# Power_board.net
KiCad netlist of a schematic drawn in EAGLE
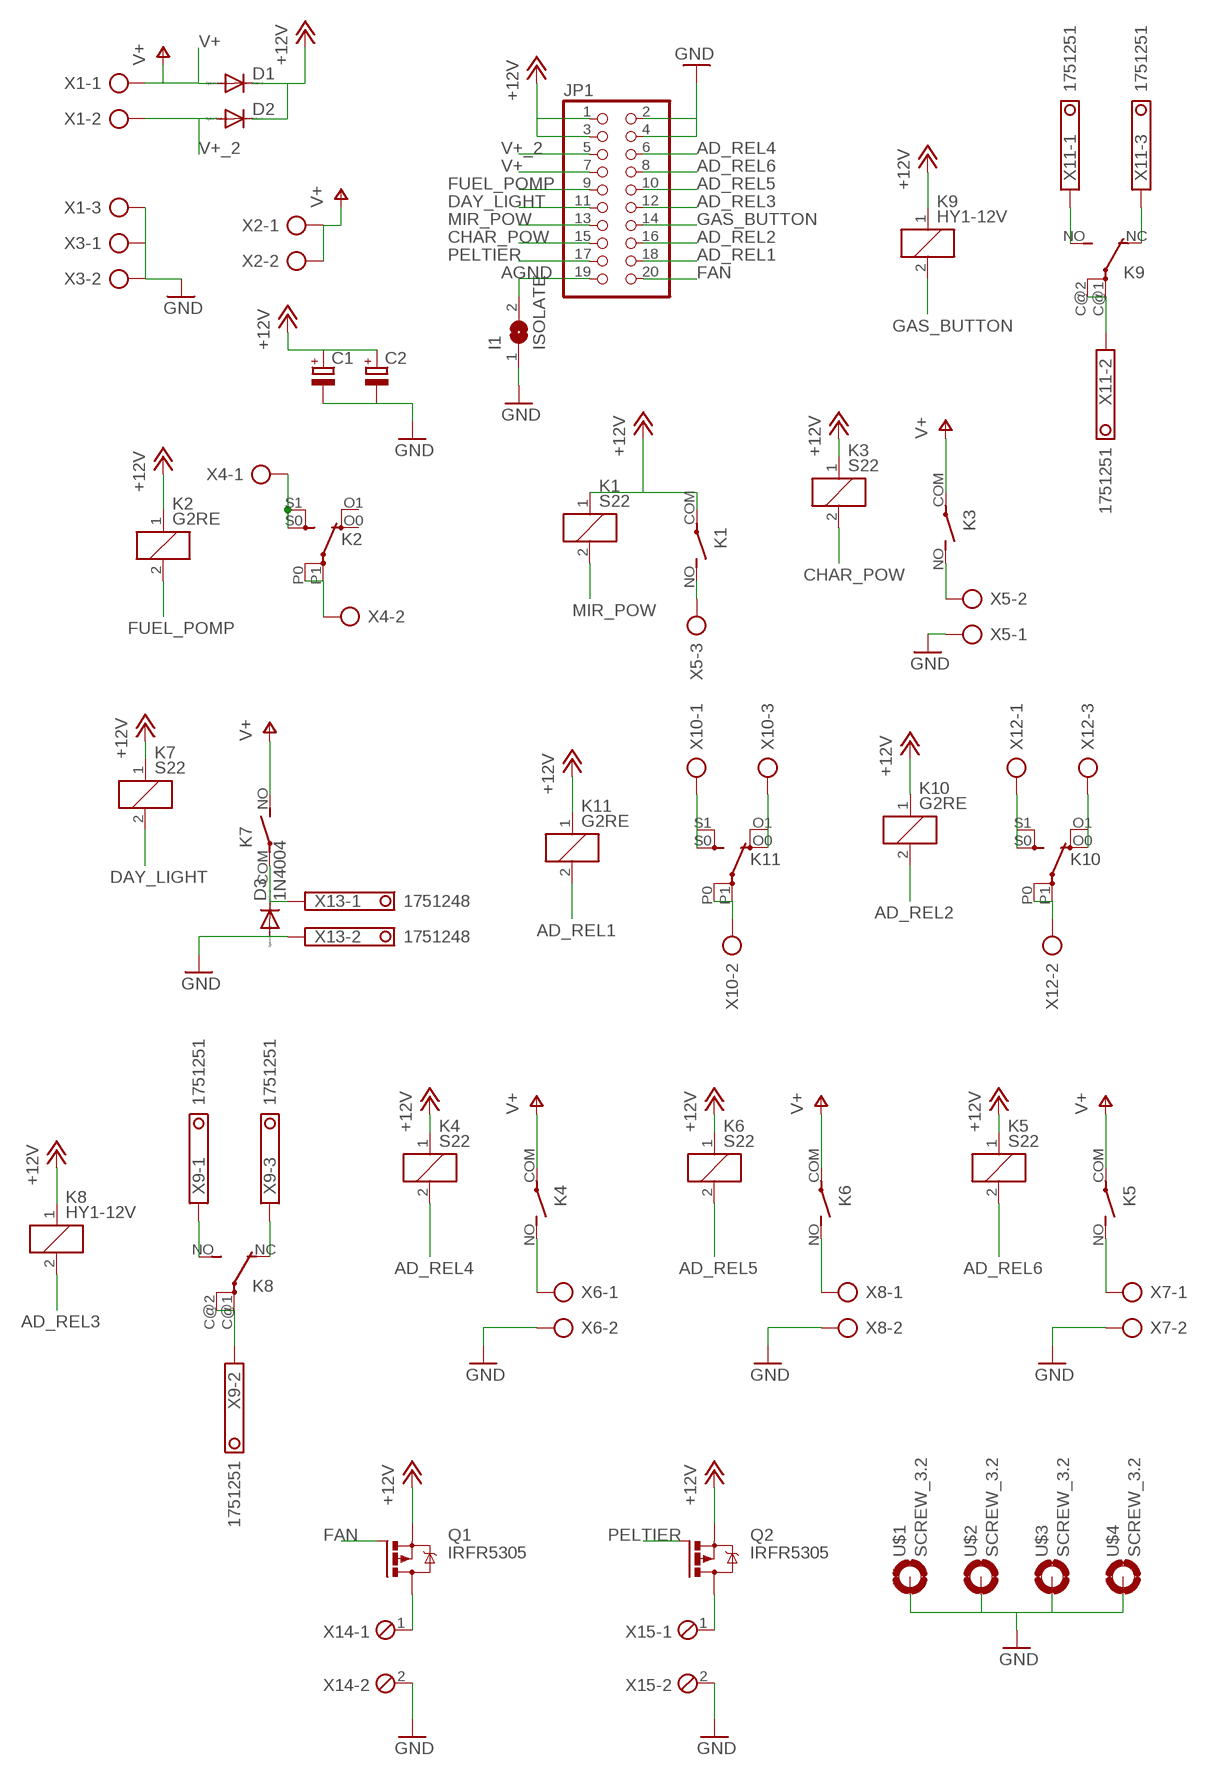
[diagram p0: schematic, sheet 1]

(export (version "E")
  (design (tool "Eeschema 10.0.6"))
  (components
    (comp (ref "C1")
      (value "CAP_HORIZ")
      (footprint "eagle-import:C075-032X103")
      (libsource (lib "eagle-import") (part "CAP_HORIZ"))
    )
    (comp (ref "C2")
      (value "CAP_HORIZ")
      (footprint "eagle-import:C075-032X103")
      (libsource (lib "eagle-import") (part "CAP_HORIZ"))
    )
    (comp (ref "D1")
      (value "DIODE-P6-15")
      (footprint "eagle-import:P6-15")
      (libsource (lib "eagle-import") (part "DIODE-P6-15"))
    )
    (comp (ref "D2")
      (value "DIODE-P6-15")
      (footprint "eagle-import:P6-15")
      (libsource (lib "eagle-import") (part "DIODE-P6-15"))
    )
    (comp (ref "D3")
      (value "1N4004")
      (footprint "eagle-import:DO41-10")
      (libsource (lib "eagle-import") (part "1N4004"))
    )
    (comp (ref "I1")
      (value "ISOLATE")
      (footprint "eagle-import:SJ")
      (libsource (lib "eagle-import") (part "ISOLATE"))
    )
    (comp (ref "JP1")
      (value "PINHD-2X10")
      (footprint "eagle-import:2X10")
      (libsource (lib "eagle-import") (part "PINHD-2X10"))
    )
    (comp (ref "K1")
      (value "S22")
      (footprint "eagle-import:LD")
      (libsource (lib "eagle-import") (part "S22"))
    )
    (comp (ref "K2")
      (value "G2RE")
      (footprint "eagle-import:G2RE")
      (libsource (lib "eagle-import") (part "G2RE"))
    )
    (comp (ref "K3")
      (value "S22")
      (footprint "eagle-import:LD")
      (libsource (lib "eagle-import") (part "S22"))
    )
    (comp (ref "K4")
      (value "S22")
      (footprint "eagle-import:LD")
      (libsource (lib "eagle-import") (part "S22"))
    )
    (comp (ref "K5")
      (value "S22")
      (footprint "eagle-import:LD")
      (libsource (lib "eagle-import") (part "S22"))
    )
    (comp (ref "K6")
      (value "S22")
      (footprint "eagle-import:LD")
      (libsource (lib "eagle-import") (part "S22"))
    )
    (comp (ref "K7")
      (value "S22")
      (footprint "eagle-import:LD")
      (libsource (lib "eagle-import") (part "S22"))
    )
    (comp (ref "K8")
      (value "HY1-12V")
      (footprint "eagle-import:HY")
      (fields (field (name "MF") "AROMAT/ MATSUSHITA"))
      (libsource (lib "eagle-import") (part "HY1-12V"))
    )
    (comp (ref "K9")
      (value "HY1-12V")
      (footprint "eagle-import:HY")
      (fields (field (name "MF") "AROMAT/ MATSUSHITA"))
      (libsource (lib "eagle-import") (part "HY1-12V"))
    )
    (comp (ref "K10")
      (value "G2RE")
      (footprint "eagle-import:G2RE")
      (libsource (lib "eagle-import") (part "G2RE"))
    )
    (comp (ref "K11")
      (value "G2RE")
      (footprint "eagle-import:G2RE")
      (libsource (lib "eagle-import") (part "G2RE"))
    )
    (comp (ref "Q1")
      (value "IRFR5305")
      (footprint "eagle-import:D-PAK_TO252AA")
      (libsource (lib "eagle-import") (part "IRF?5305R"))
    )
    (comp (ref "Q2")
      (value "IRFR5305")
      (footprint "eagle-import:D-PAK_TO252AA")
      (libsource (lib "eagle-import") (part "IRF?5305R"))
    )
    (comp (ref "U$1")
      (value "SCREW_3.2")
      (footprint "eagle-import:3,2-PAD")
      (libsource (lib "eagle-import") (part "SCREW_3.2"))
    )
    (comp (ref "U$2")
      (value "SCREW_3.2")
      (footprint "eagle-import:3,2-PAD")
      (libsource (lib "eagle-import") (part "SCREW_3.2"))
    )
    (comp (ref "U$3")
      (value "SCREW_3.2")
      (footprint "eagle-import:3,2-PAD")
      (libsource (lib "eagle-import") (part "SCREW_3.2"))
    )
    (comp (ref "U$4")
      (value "SCREW_3.2")
      (footprint "eagle-import:3,2-PAD")
      (libsource (lib "eagle-import") (part "SCREW_3.2"))
    )
    (comp (ref "X1")
      (value "AK500/3")
      (footprint "eagle-import:AK500_3")
      (libsource (lib "eagle-import") (part "AK500/3"))
    )
    (comp (ref "X2")
      (value "AK500/2")
      (footprint "eagle-import:AK500_2")
      (libsource (lib "eagle-import") (part "AK500/2"))
    )
    (comp (ref "X3")
      (value "AK500/2")
      (footprint "eagle-import:AK500_2")
      (libsource (lib "eagle-import") (part "AK500/2"))
    )
    (comp (ref "X4")
      (value "AK500/2")
      (footprint "eagle-import:AK500_2")
      (libsource (lib "eagle-import") (part "AK500/2"))
    )
    (comp (ref "X5")
      (value "AK500/3")
      (footprint "eagle-import:AK500_3")
      (libsource (lib "eagle-import") (part "AK500/3"))
    )
    (comp (ref "X6")
      (value "AK500/2")
      (footprint "eagle-import:AK500_2")
      (libsource (lib "eagle-import") (part "AK500/2"))
    )
    (comp (ref "X7")
      (value "AK500/2")
      (footprint "eagle-import:AK500_2")
      (libsource (lib "eagle-import") (part "AK500/2"))
    )
    (comp (ref "X8")
      (value "AK500/2")
      (footprint "eagle-import:AK500_2")
      (libsource (lib "eagle-import") (part "AK500/2"))
    )
    (comp (ref "X9")
      (value "1751251")
      (footprint "eagle-import:1751251")
      (libsource (lib "eagle-import") (part "1751251"))
    )
    (comp (ref "X10")
      (value "AK500/3")
      (footprint "eagle-import:AK500_3")
      (libsource (lib "eagle-import") (part "AK500/3"))
    )
    (comp (ref "X11")
      (value "1751251")
      (footprint "eagle-import:1751251")
      (libsource (lib "eagle-import") (part "1751251"))
    )
    (comp (ref "X12")
      (value "AK500/3")
      (footprint "eagle-import:AK500_3")
      (libsource (lib "eagle-import") (part "AK500/3"))
    )
    (comp (ref "X13")
      (value "1751248")
      (footprint "eagle-import:1751248")
      (libsource (lib "eagle-import") (part "1751248"))
    )
    (comp (ref "X14")
      (value "MPT2")
      (footprint "eagle-import:2POL254")
      (libsource (lib "eagle-import") (part "MPT2"))
    )
    (comp (ref "X15")
      (value "MPT2")
      (footprint "eagle-import:2POL254")
      (libsource (lib "eagle-import") (part "MPT2"))
    )
  )
  (nets
    (net (code "1") (name "+12V") (class "Default")
      (node (ref "C1") (pin "1") (pinfunction "+_1") (pintype "passive"))
      (node (ref "C2") (pin "1") (pinfunction "+_1") (pintype "passive"))
      (node (ref "D1") (pin "C") (pinfunction "C_C") (pintype "passive"))
      (node (ref "D2") (pin "C") (pinfunction "C_C") (pintype "passive"))
      (node (ref "JP1") (pin "1") (pinfunction "1_1") (pintype "passive"))
      (node (ref "JP1") (pin "3") (pinfunction "3_3") (pintype "passive"))
      (node (ref "K1") (pin "1") (pinfunction "1_1") (pintype "passive"))
      (node (ref "K1") (pin "COM") (pinfunction "P_COM") (pintype "passive"))
      (node (ref "K10") (pin "1") (pinfunction "1_1") (pintype "passive"))
      (node (ref "K11") (pin "1") (pinfunction "1_1") (pintype "passive"))
      (node (ref "K2") (pin "1") (pinfunction "1_1") (pintype "passive"))
      (node (ref "K3") (pin "1") (pinfunction "1_1") (pintype "passive"))
      (node (ref "K4") (pin "1") (pinfunction "1_1") (pintype "passive"))
      (node (ref "K5") (pin "1") (pinfunction "1_1") (pintype "passive"))
      (node (ref "K6") (pin "1") (pinfunction "1_1") (pintype "passive"))
      (node (ref "K7") (pin "1") (pinfunction "1_1") (pintype "passive"))
      (node (ref "K8") (pin "1") (pinfunction "1_1") (pintype "passive"))
      (node (ref "K9") (pin "1") (pinfunction "1_1") (pintype "passive"))
      (node (ref "Q1") (pin "3") (pinfunction "S_3") (pintype "passive"))
      (node (ref "Q2") (pin "3") (pinfunction "S_3") (pintype "passive"))
    )
    (net (code "2") (name "/AD_REL1") (class "Default")
      (node (ref "JP1") (pin "18") (pinfunction "18_18") (pintype "passive"))
      (node (ref "K11") (pin "2") (pinfunction "2_2") (pintype "passive"))
    )
    (net (code "3") (name "/AD_REL2") (class "Default")
      (node (ref "JP1") (pin "16") (pinfunction "16_16") (pintype "passive"))
      (node (ref "K10") (pin "2") (pinfunction "2_2") (pintype "passive"))
    )
    (net (code "4") (name "/AD_REL3") (class "Default")
      (node (ref "JP1") (pin "12") (pinfunction "12_12") (pintype "passive"))
      (node (ref "K8") (pin "2") (pinfunction "2_2") (pintype "passive"))
    )
    (net (code "5") (name "/AD_REL4") (class "Default")
      (node (ref "JP1") (pin "6") (pinfunction "6_6") (pintype "passive"))
      (node (ref "K4") (pin "2") (pinfunction "2_2") (pintype "passive"))
    )
    (net (code "6") (name "/AD_REL5") (class "Default")
      (node (ref "JP1") (pin "10") (pinfunction "10_10") (pintype "passive"))
      (node (ref "K6") (pin "2") (pinfunction "2_2") (pintype "passive"))
    )
    (net (code "7") (name "/AD_REL6") (class "Default")
      (node (ref "JP1") (pin "8") (pinfunction "8_8") (pintype "passive"))
      (node (ref "K5") (pin "2") (pinfunction "2_2") (pintype "passive"))
    )
    (net (code "8") (name "/AGND") (class "Default")
      (node (ref "I1") (pin "2") (pinfunction "2_2") (pintype "passive"))
      (node (ref "JP1") (pin "19") (pinfunction "19_19") (pintype "passive"))
    )
    (net (code "9") (name "/CHAR_POW") (class "Default")
      (node (ref "JP1") (pin "15") (pinfunction "15_15") (pintype "passive"))
      (node (ref "K3") (pin "2") (pinfunction "2_2") (pintype "passive"))
    )
    (net (code "10") (name "/DAY_LIGHT") (class "Default")
      (node (ref "JP1") (pin "11") (pinfunction "11_11") (pintype "passive"))
      (node (ref "K7") (pin "2") (pinfunction "2_2") (pintype "passive"))
    )
    (net (code "11") (name "/FAN") (class "Default")
      (node (ref "JP1") (pin "20") (pinfunction "20_20") (pintype "passive"))
      (node (ref "Q1") (pin "1") (pinfunction "G_1") (pintype "passive"))
    )
    (net (code "12") (name "/FUEL_POMP") (class "Default")
      (node (ref "JP1") (pin "9") (pinfunction "9_9") (pintype "passive"))
      (node (ref "K2") (pin "2") (pinfunction "2_2") (pintype "passive"))
    )
    (net (code "13") (name "/GAS_BUTTON") (class "Default")
      (node (ref "JP1") (pin "14") (pinfunction "14_14") (pintype "passive"))
      (node (ref "K9") (pin "2") (pinfunction "2_2") (pintype "passive"))
    )
    (net (code "14") (name "/MIR_POW") (class "Default")
      (node (ref "JP1") (pin "13") (pinfunction "13_13") (pintype "passive"))
      (node (ref "K1") (pin "2") (pinfunction "2_2") (pintype "passive"))
    )
    (net (code "15") (name "/PELTIER") (class "Default")
      (node (ref "JP1") (pin "17") (pinfunction "17_17") (pintype "passive"))
      (node (ref "Q2") (pin "1") (pinfunction "G_1") (pintype "passive"))
    )
    (net (code "16") (name "/V+_2") (class "Default")
      (node (ref "D2") (pin "A") (pinfunction "A_A") (pintype "passive"))
      (node (ref "JP1") (pin "5") (pinfunction "5_5") (pintype "passive"))
      (node (ref "X1") (pin "2") (pinfunction "KL_2") (pintype "passive"))
    )
    (net (code "17") (name "GND") (class "Default")
      (node (ref "C1") (pin "2") (pinfunction "-_2") (pintype "passive"))
      (node (ref "C2") (pin "2") (pinfunction "-_2") (pintype "passive"))
      (node (ref "D3") (pin "A") (pinfunction "A_A") (pintype "passive"))
      (node (ref "I1") (pin "1") (pinfunction "1_1") (pintype "passive"))
      (node (ref "JP1") (pin "2") (pinfunction "2_2") (pintype "passive"))
      (node (ref "JP1") (pin "4") (pinfunction "4_4") (pintype "passive"))
      (node (ref "U$1") (pin "B3,2") (pinfunction "MOUNT_B3,2") (pintype "passive"))
      (node (ref "U$2") (pin "B3,2") (pinfunction "MOUNT_B3,2") (pintype "passive"))
      (node (ref "U$3") (pin "B3,2") (pinfunction "MOUNT_B3,2") (pintype "passive"))
      (node (ref "U$4") (pin "B3,2") (pinfunction "MOUNT_B3,2") (pintype "passive"))
      (node (ref "X1") (pin "3") (pinfunction "KL_3") (pintype "passive"))
      (node (ref "X13") (pin "2") (pinfunction "K_2") (pintype "passive"))
      (node (ref "X14") (pin "2") (pinfunction "1_2") (pintype "passive"))
      (node (ref "X15") (pin "2") (pinfunction "1_2") (pintype "passive"))
      (node (ref "X3") (pin "1") (pinfunction "KL_1") (pintype "passive"))
      (node (ref "X3") (pin "2") (pinfunction "KL_2") (pintype "passive"))
      (node (ref "X5") (pin "1") (pinfunction "KL_1") (pintype "passive"))
      (node (ref "X6") (pin "2") (pinfunction "KL_2") (pintype "passive"))
      (node (ref "X7") (pin "2") (pinfunction "KL_2") (pintype "passive"))
      (node (ref "X8") (pin "2") (pinfunction "KL_2") (pintype "passive"))
    )
    (net (code "18") (name "Net-(K1A-S)") (class "Default")
      (node (ref "K1") (pin "NO") (pinfunction "S_NO") (pintype "passive"))
      (node (ref "X5") (pin "3") (pinfunction "KL_3") (pintype "passive"))
    )
    (net (code "19") (name "Net-(K3A-S)") (class "Default")
      (node (ref "K3") (pin "NO") (pinfunction "S_NO") (pintype "passive"))
      (node (ref "X5") (pin "2") (pinfunction "KL_2") (pintype "passive"))
    )
    (net (code "20") (name "Net-(K4A-S)") (class "Default")
      (node (ref "K4") (pin "NO") (pinfunction "S_NO") (pintype "passive"))
      (node (ref "X6") (pin "1") (pinfunction "KL_1") (pintype "passive"))
    )
    (net (code "21") (name "Net-(K5A-S)") (class "Default")
      (node (ref "K5") (pin "NO") (pinfunction "S_NO") (pintype "passive"))
      (node (ref "X7") (pin "1") (pinfunction "KL_1") (pintype "passive"))
    )
    (net (code "22") (name "Net-(K6A-S)") (class "Default")
      (node (ref "K6") (pin "NO") (pinfunction "S_NO") (pintype "passive"))
      (node (ref "X8") (pin "1") (pinfunction "KL_1") (pintype "passive"))
    )
    (net (code "23") (name "Net-(K7A-P)") (class "Default")
      (node (ref "D3") (pin "C") (pinfunction "C_C") (pintype "passive"))
      (node (ref "K7") (pin "COM") (pinfunction "P_COM") (pintype "passive"))
      (node (ref "X13") (pin "1") (pinfunction "K_1") (pintype "passive"))
    )
    (net (code "24") (name "Net-(K8B-O)") (class "Default")
      (node (ref "K8") (pin "NC") (pinfunction "O_NC") (pintype "passive"))
      (node (ref "X9") (pin "3") (pinfunction "K_3") (pintype "passive"))
    )
    (net (code "25") (name "Net-(K8B-S)") (class "Default")
      (node (ref "K8") (pin "NO") (pinfunction "S_NO") (pintype "passive"))
      (node (ref "X9") (pin "1") (pinfunction "K_1") (pintype "passive"))
    )
    (net (code "26") (name "Net-(K9B-O)") (class "Default")
      (node (ref "K9") (pin "NC") (pinfunction "O_NC") (pintype "passive"))
      (node (ref "X11") (pin "3") (pinfunction "K_3") (pintype "passive"))
    )
    (net (code "27") (name "Net-(K9B-S)") (class "Default")
      (node (ref "K9") (pin "NO") (pinfunction "S_NO") (pintype "passive"))
      (node (ref "X11") (pin "1") (pinfunction "K_1") (pintype "passive"))
    )
    (net (code "28") (name "Net-(Q1-D)") (class "Default")
      (node (ref "Q1") (pin "4") (pinfunction "D_4") (pintype "passive"))
      (node (ref "X14") (pin "1") (pinfunction "1_1") (pintype "passive"))
    )
    (net (code "29") (name "Net-(Q2-D)") (class "Default")
      (node (ref "Q2") (pin "4") (pinfunction "D_4") (pintype "passive"))
      (node (ref "X15") (pin "1") (pinfunction "1_1") (pintype "passive"))
    )
    (net (code "30") (name "Net-(X4A-KL)") (class "Default")
      (node (ref "K2") (pin "S0") (pinfunction "S_S0") (pintype "passive"))
      (node (ref "K2") (pin "S1") (pinfunction "S_S1") (pintype "passive"))
      (node (ref "X4") (pin "1") (pinfunction "KL_1") (pintype "passive"))
    )
    (net (code "31") (name "Net-(X4B-KL)") (class "Default")
      (node (ref "K2") (pin "P0") (pinfunction "P_P0") (pintype "passive"))
      (node (ref "K2") (pin "P1") (pinfunction "P_P1") (pintype "passive"))
      (node (ref "X4") (pin "2") (pinfunction "KL_2") (pintype "passive"))
    )
    (net (code "32") (name "Net-(X9B-K)") (class "Default")
      (node (ref "K8") (pin "C@1") (pinfunction "P_C@1") (pintype "passive"))
      (node (ref "K8") (pin "C@2") (pinfunction "P_C@2") (pintype "passive"))
      (node (ref "X9") (pin "2") (pinfunction "K_2") (pintype "passive"))
    )
    (net (code "33") (name "Net-(X10A-KL)") (class "Default")
      (node (ref "K11") (pin "S0") (pinfunction "S_S0") (pintype "passive"))
      (node (ref "K11") (pin "S1") (pinfunction "S_S1") (pintype "passive"))
      (node (ref "X10") (pin "1") (pinfunction "KL_1") (pintype "passive"))
    )
    (net (code "34") (name "Net-(X10B-KL)") (class "Default")
      (node (ref "K11") (pin "P0") (pinfunction "P_P0") (pintype "passive"))
      (node (ref "K11") (pin "P1") (pinfunction "P_P1") (pintype "passive"))
      (node (ref "X10") (pin "2") (pinfunction "KL_2") (pintype "passive"))
    )
    (net (code "35") (name "Net-(X10C-KL)") (class "Default")
      (node (ref "K11") (pin "O0") (pinfunction "O_O0") (pintype "passive"))
      (node (ref "K11") (pin "O1") (pinfunction "O_O1") (pintype "passive"))
      (node (ref "X10") (pin "3") (pinfunction "KL_3") (pintype "passive"))
    )
    (net (code "36") (name "Net-(X11B-K)") (class "Default")
      (node (ref "K9") (pin "C@1") (pinfunction "P_C@1") (pintype "passive"))
      (node (ref "K9") (pin "C@2") (pinfunction "P_C@2") (pintype "passive"))
      (node (ref "X11") (pin "2") (pinfunction "K_2") (pintype "passive"))
    )
    (net (code "37") (name "Net-(X12A-KL)") (class "Default")
      (node (ref "K10") (pin "S0") (pinfunction "S_S0") (pintype "passive"))
      (node (ref "K10") (pin "S1") (pinfunction "S_S1") (pintype "passive"))
      (node (ref "X12") (pin "1") (pinfunction "KL_1") (pintype "passive"))
    )
    (net (code "38") (name "Net-(X12B-KL)") (class "Default")
      (node (ref "K10") (pin "P0") (pinfunction "P_P0") (pintype "passive"))
      (node (ref "K10") (pin "P1") (pinfunction "P_P1") (pintype "passive"))
      (node (ref "X12") (pin "2") (pinfunction "KL_2") (pintype "passive"))
    )
    (net (code "39") (name "Net-(X12C-KL)") (class "Default")
      (node (ref "K10") (pin "O0") (pinfunction "O_O0") (pintype "passive"))
      (node (ref "K10") (pin "O1") (pinfunction "O_O1") (pintype "passive"))
      (node (ref "X12") (pin "3") (pinfunction "KL_3") (pintype "passive"))
    )
    (net (code "40") (name "V+") (class "Default")
      (node (ref "D1") (pin "A") (pinfunction "A_A") (pintype "passive"))
      (node (ref "JP1") (pin "7") (pinfunction "7_7") (pintype "passive"))
      (node (ref "K3") (pin "COM") (pinfunction "P_COM") (pintype "passive"))
      (node (ref "K4") (pin "COM") (pinfunction "P_COM") (pintype "passive"))
      (node (ref "K5") (pin "COM") (pinfunction "P_COM") (pintype "passive"))
      (node (ref "K6") (pin "COM") (pinfunction "P_COM") (pintype "passive"))
      (node (ref "K7") (pin "NO") (pinfunction "S_NO") (pintype "passive"))
      (node (ref "X1") (pin "1") (pinfunction "KL_1") (pintype "passive"))
      (node (ref "X2") (pin "1") (pinfunction "KL_1") (pintype "passive"))
      (node (ref "X2") (pin "2") (pinfunction "KL_2") (pintype "passive"))
    )
    (net (code "41") (name "unconnected-(K2B-O-PadO0)") (class "Default")
      (node (ref "K2") (pin "O0") (pinfunction "O_O0") (pintype "passive"))
    )
    (net (code "42") (name "unconnected-(K2B-O-PadO1)") (class "Default")
      (node (ref "K2") (pin "O1") (pinfunction "O_O1") (pintype "passive"))
    )
  )
)
